# TMMOD-BREAKOUT-v1_1.net
KiCad netlist of a schematic drawn in EAGLE
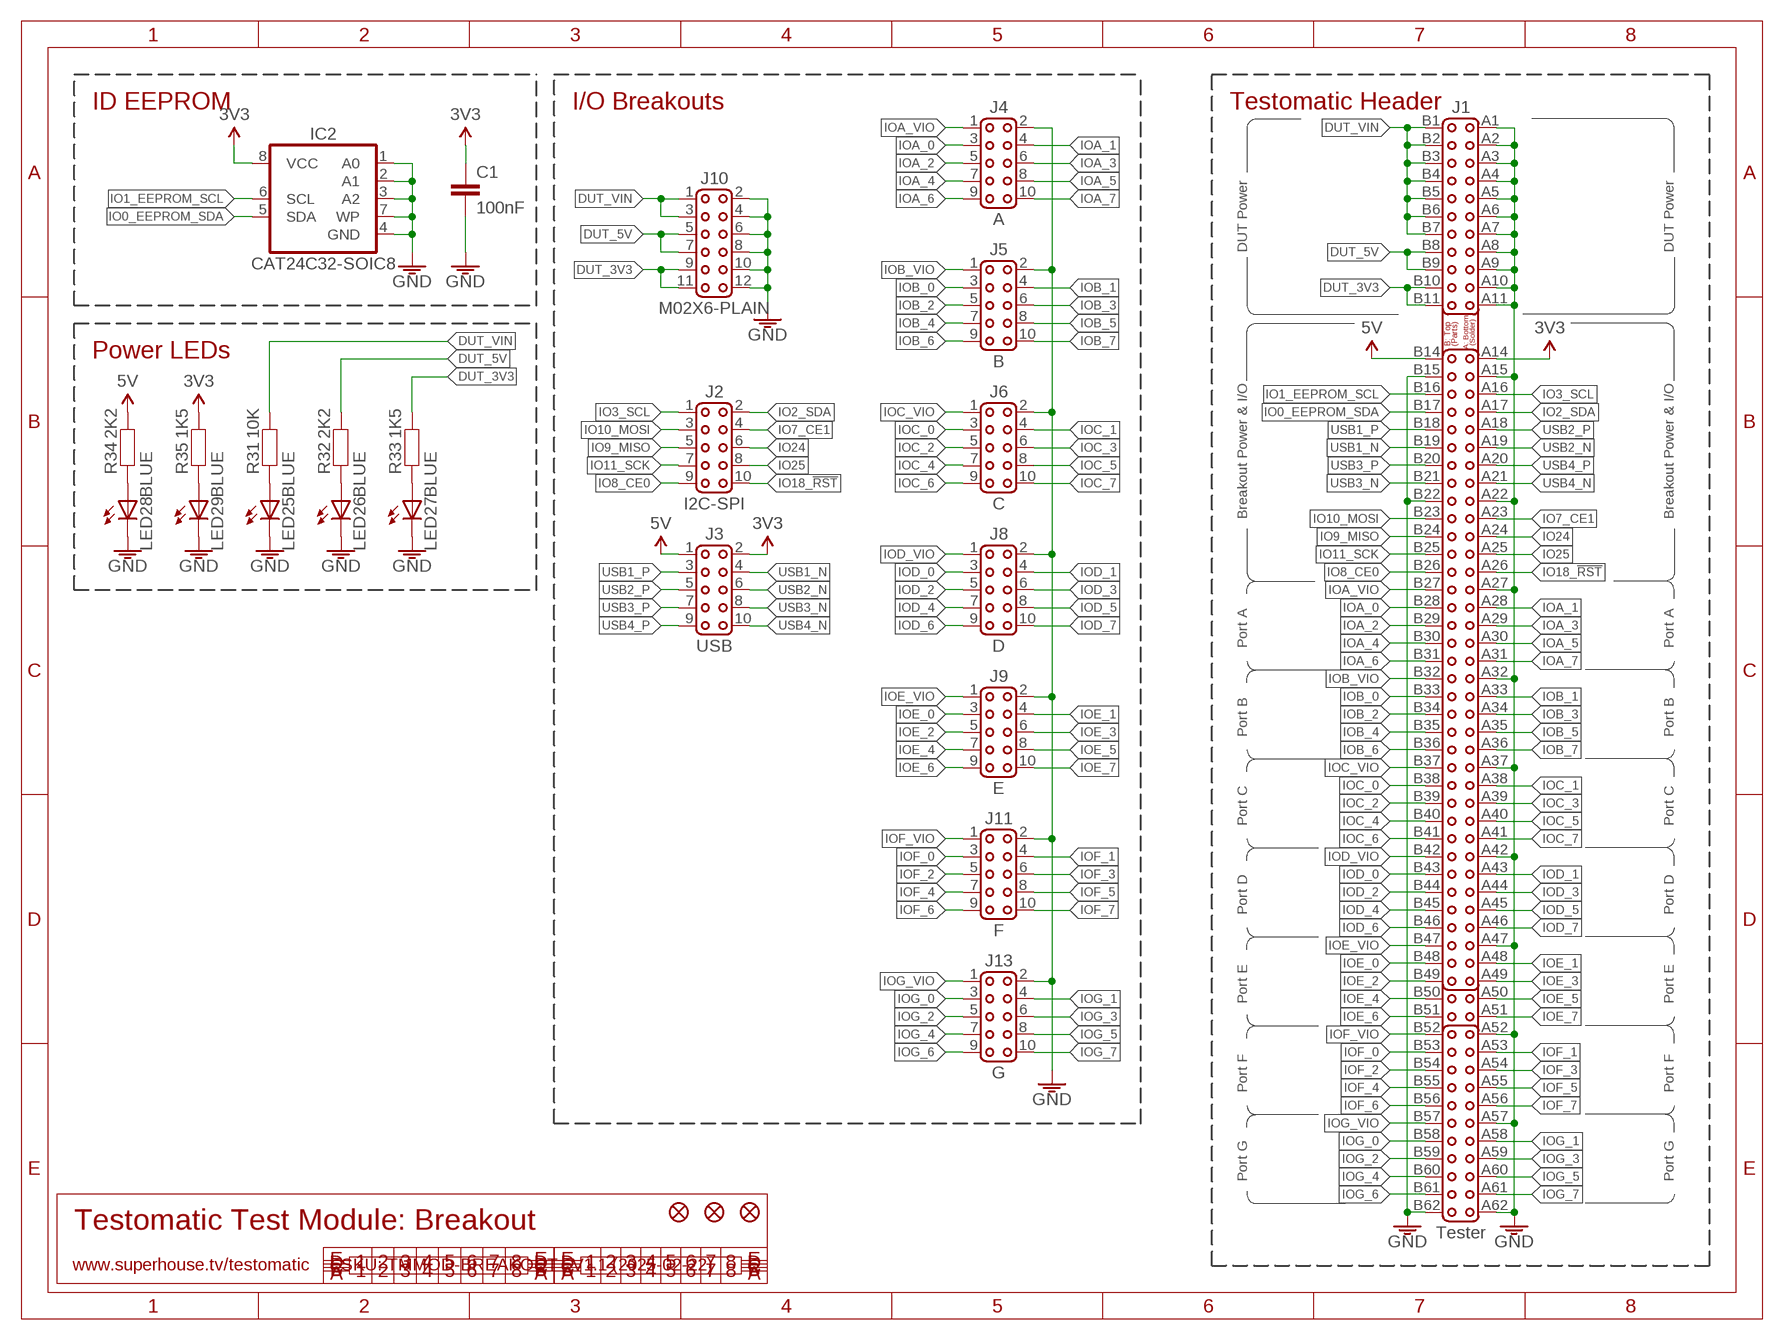
[diagram p0: schematic, sheet 1]

(export (version "E")
  (design (tool "Eeschema 10.0.6"))
  (components
    (comp (ref "C1")
      (value "100nF")
      (footprint "eagle-import:C0603")
      (libsource (lib "eagle-import") (part "CAP0603"))
    )
    (comp (ref "FID1")
      (value "FIDUCIAL1X2.5")
      (footprint "eagle-import:FIDUCIAL-1X2.5")
      (libsource (lib "eagle-import") (part "FIDUCIAL1X2.5"))
    )
    (comp (ref "FID2")
      (value "FIDUCIAL1X2.5")
      (footprint "eagle-import:FIDUCIAL-1X2.5")
      (libsource (lib "eagle-import") (part "FIDUCIAL1X2.5"))
    )
    (comp (ref "FID3")
      (value "FIDUCIAL1X2.5")
      (footprint "eagle-import:FIDUCIAL-1X2.5")
      (libsource (lib "eagle-import") (part "FIDUCIAL1X2.5"))
    )
    (comp (ref "IC2")
      (value "CAT24C32-SOIC8")
      (footprint "eagle-import:SOIC8")
      (libsource (lib "eagle-import") (part "CAT24C32-SOIC8"))
    )
    (comp (ref "J1")
      (value "Tester")
      (footprint "eagle-import:PCI-CARD")
      (libsource (lib "eagle-import") (part "PCI-CARD"))
    )
    (comp (ref "J2")
      (value "I2C-SPI")
      (footprint "eagle-import:2X05-2.54-PLAIN")
      (libsource (lib "eagle-import") (part "M02X5-PLAIN"))
    )
    (comp (ref "J3")
      (value "USB")
      (footprint "eagle-import:2X05-2.54-PLAIN")
      (libsource (lib "eagle-import") (part "M02X5-PLAIN"))
    )
    (comp (ref "J4")
      (value "A")
      (footprint "eagle-import:2X05-2.54-PLAIN")
      (libsource (lib "eagle-import") (part "M02X5-PLAIN"))
    )
    (comp (ref "J5")
      (value "B")
      (footprint "eagle-import:2X05-2.54-PLAIN")
      (libsource (lib "eagle-import") (part "M02X5-PLAIN"))
    )
    (comp (ref "J6")
      (value "C")
      (footprint "eagle-import:2X05-2.54-PLAIN")
      (libsource (lib "eagle-import") (part "M02X5-PLAIN"))
    )
    (comp (ref "J8")
      (value "D")
      (footprint "eagle-import:2X05-2.54-PLAIN")
      (libsource (lib "eagle-import") (part "M02X5-PLAIN"))
    )
    (comp (ref "J9")
      (value "E")
      (footprint "eagle-import:2X05-2.54-PLAIN")
      (libsource (lib "eagle-import") (part "M02X5-PLAIN"))
    )
    (comp (ref "J10")
      (value "M02X6-PLAIN")
      (footprint "eagle-import:2X06")
      (libsource (lib "eagle-import") (part "M02X6-PLAIN"))
    )
    (comp (ref "J11")
      (value "F")
      (footprint "eagle-import:2X05-2.54-PLAIN")
      (libsource (lib "eagle-import") (part "M02X5-PLAIN"))
    )
    (comp (ref "J13")
      (value "G")
      (footprint "eagle-import:2X05-2.54-PLAIN")
      (libsource (lib "eagle-import") (part "M02X5-PLAIN"))
    )
    (comp (ref "LED25")
      (value "BLUE")
      (footprint "eagle-import:LED-0603")
      (libsource (lib "eagle-import") (part "LED0603"))
    )
    (comp (ref "LED26")
      (value "BLUE")
      (footprint "eagle-import:LED-0603")
      (libsource (lib "eagle-import") (part "LED0603"))
    )
    (comp (ref "LED27")
      (value "BLUE")
      (footprint "eagle-import:LED-0603")
      (libsource (lib "eagle-import") (part "LED0603"))
    )
    (comp (ref "LED28")
      (value "BLUE")
      (footprint "eagle-import:LED-0603")
      (libsource (lib "eagle-import") (part "LED0603"))
    )
    (comp (ref "LED29")
      (value "BLUE")
      (footprint "eagle-import:LED-0603")
      (libsource (lib "eagle-import") (part "LED0603"))
    )
    (comp (ref "R31")
      (value "10K")
      (footprint "eagle-import:R0603")
      (libsource (lib "eagle-import") (part "RESISTOR0603"))
    )
    (comp (ref "R32")
      (value "2K2")
      (footprint "eagle-import:R0603")
      (libsource (lib "eagle-import") (part "RESISTOR0603"))
    )
    (comp (ref "R33")
      (value "1K5")
      (footprint "eagle-import:R0603")
      (libsource (lib "eagle-import") (part "RESISTOR0603"))
    )
    (comp (ref "R34")
      (value "2K2")
      (footprint "eagle-import:R0603")
      (libsource (lib "eagle-import") (part "RESISTOR0603"))
    )
    (comp (ref "R35")
      (value "1K5")
      (footprint "eagle-import:R0603")
      (libsource (lib "eagle-import") (part "RESISTOR0603"))
    )
  )
  (nets
    (net (code "1") (name "/IO18_~{RST}") (class "Default")
      (node (ref "J1") (pin "A26") (pinfunction "A26_A26") (pintype "passive"))
      (node (ref "J2") (pin "10") (pinfunction "10_10") (pintype "passive"))
    )
    (net (code "2") (name "3.3V") (class "Default")
      (node (ref "C1") (pin "1") (pinfunction "1_1") (pintype "passive"))
      (node (ref "IC2") (pin "8") (pinfunction "VCC_8") (pintype "power_in"))
      (node (ref "J1") (pin "A14") (pinfunction "A14_A14") (pintype "passive"))
      (node (ref "J3") (pin "2") (pinfunction "2_2") (pintype "passive"))
      (node (ref "R35") (pin "2") (pinfunction "2_2") (pintype "passive"))
    )
    (net (code "3") (name "5V") (class "Default")
      (node (ref "J1") (pin "B14") (pinfunction "B14_B14") (pintype "passive"))
      (node (ref "J3") (pin "1") (pinfunction "1_1") (pintype "passive"))
      (node (ref "R34") (pin "2") (pinfunction "2_2") (pintype "passive"))
    )
    (net (code "4") (name "DUT_3V3") (class "Default")
      (node (ref "J1") (pin "B10") (pinfunction "B10_B10") (pintype "passive"))
      (node (ref "J1") (pin "B11") (pinfunction "B11_B11") (pintype "passive"))
      (node (ref "J10") (pin "11") (pinfunction "11_11") (pintype "passive"))
      (node (ref "J10") (pin "9") (pinfunction "9_9") (pintype "passive"))
      (node (ref "R33") (pin "2") (pinfunction "2_2") (pintype "passive"))
    )
    (net (code "5") (name "DUT_5V") (class "Default")
      (node (ref "J1") (pin "B8") (pinfunction "B8_B8") (pintype "passive"))
      (node (ref "J1") (pin "B9") (pinfunction "B9_B9") (pintype "passive"))
      (node (ref "J10") (pin "5") (pinfunction "5_5") (pintype "passive"))
      (node (ref "J10") (pin "7") (pinfunction "7_7") (pintype "passive"))
      (node (ref "R32") (pin "2") (pinfunction "2_2") (pintype "passive"))
    )
    (net (code "6") (name "DUT_VIN") (class "Default")
      (node (ref "J1") (pin "B1") (pinfunction "B1_B1") (pintype "passive"))
      (node (ref "J1") (pin "B2") (pinfunction "B2_B2") (pintype "passive"))
      (node (ref "J1") (pin "B3") (pinfunction "B3_B3") (pintype "passive"))
      (node (ref "J1") (pin "B4") (pinfunction "B4_B4") (pintype "passive"))
      (node (ref "J1") (pin "B5") (pinfunction "B5_B5") (pintype "passive"))
      (node (ref "J1") (pin "B6") (pinfunction "B6_B6") (pintype "passive"))
      (node (ref "J1") (pin "B7") (pinfunction "B7_B7") (pintype "passive"))
      (node (ref "J10") (pin "1") (pinfunction "1_1") (pintype "passive"))
      (node (ref "J10") (pin "3") (pinfunction "3_3") (pintype "passive"))
      (node (ref "R31") (pin "2") (pinfunction "2_2") (pintype "passive"))
    )
    (net (code "7") (name "GND") (class "Default")
      (node (ref "C1") (pin "2") (pinfunction "2_2") (pintype "passive"))
      (node (ref "IC2") (pin "1") (pinfunction "A0_1") (pintype "input"))
      (node (ref "IC2") (pin "2") (pinfunction "A1_2") (pintype "input"))
      (node (ref "IC2") (pin "3") (pinfunction "A2_3") (pintype "input"))
      (node (ref "IC2") (pin "4") (pinfunction "GND_4") (pintype "power_in"))
      (node (ref "IC2") (pin "7") (pinfunction "WP_7") (pintype "bidirectional"))
      (node (ref "J1") (pin "A1") (pinfunction "A1_A1") (pintype "passive"))
      (node (ref "J1") (pin "A10") (pinfunction "A10_A10") (pintype "passive"))
      (node (ref "J1") (pin "A11") (pinfunction "A11_A11") (pintype "passive"))
      (node (ref "J1") (pin "A15") (pinfunction "A15_A15") (pintype "passive"))
      (node (ref "J1") (pin "A2") (pinfunction "A2_A2") (pintype "passive"))
      (node (ref "J1") (pin "A22") (pinfunction "A22_A22") (pintype "passive"))
      (node (ref "J1") (pin "A27") (pinfunction "A27_A27") (pintype "passive"))
      (node (ref "J1") (pin "A3") (pinfunction "A3_A3") (pintype "passive"))
      (node (ref "J1") (pin "A32") (pinfunction "A32_A32") (pintype "passive"))
      (node (ref "J1") (pin "A37") (pinfunction "A37_A37") (pintype "passive"))
      (node (ref "J1") (pin "A4") (pinfunction "A4_A4") (pintype "passive"))
      (node (ref "J1") (pin "A42") (pinfunction "A42_A42") (pintype "passive"))
      (node (ref "J1") (pin "A47") (pinfunction "A47_A47") (pintype "passive"))
      (node (ref "J1") (pin "A5") (pinfunction "A5_A5") (pintype "passive"))
      (node (ref "J1") (pin "A52") (pinfunction "A52_A52") (pintype "passive"))
      (node (ref "J1") (pin "A57") (pinfunction "A57_A57") (pintype "passive"))
      (node (ref "J1") (pin "A6") (pinfunction "A6_A6") (pintype "passive"))
      (node (ref "J1") (pin "A62") (pinfunction "A62_A62") (pintype "passive"))
      (node (ref "J1") (pin "A7") (pinfunction "A7_A7") (pintype "passive"))
      (node (ref "J1") (pin "A8") (pinfunction "A8_A8") (pintype "passive"))
      (node (ref "J1") (pin "A9") (pinfunction "A9_A9") (pintype "passive"))
      (node (ref "J1") (pin "B15") (pinfunction "B15_B15") (pintype "passive"))
      (node (ref "J1") (pin "B22") (pinfunction "B22_B22") (pintype "passive"))
      (node (ref "J1") (pin "B62") (pinfunction "B62_B62") (pintype "passive"))
      (node (ref "J10") (pin "10") (pinfunction "10_10") (pintype "passive"))
      (node (ref "J10") (pin "12") (pinfunction "12_12") (pintype "passive"))
      (node (ref "J10") (pin "2") (pinfunction "2_2") (pintype "passive"))
      (node (ref "J10") (pin "4") (pinfunction "4_4") (pintype "passive"))
      (node (ref "J10") (pin "6") (pinfunction "6_6") (pintype "passive"))
      (node (ref "J10") (pin "8") (pinfunction "8_8") (pintype "passive"))
      (node (ref "J11") (pin "2") (pinfunction "2_2") (pintype "passive"))
      (node (ref "J13") (pin "2") (pinfunction "2_2") (pintype "passive"))
      (node (ref "J4") (pin "2") (pinfunction "2_2") (pintype "passive"))
      (node (ref "J5") (pin "2") (pinfunction "2_2") (pintype "passive"))
      (node (ref "J6") (pin "2") (pinfunction "2_2") (pintype "passive"))
      (node (ref "J8") (pin "2") (pinfunction "2_2") (pintype "passive"))
      (node (ref "J9") (pin "2") (pinfunction "2_2") (pintype "passive"))
      (node (ref "LED25") (pin "C") (pinfunction "C_C") (pintype "passive"))
      (node (ref "LED26") (pin "C") (pinfunction "C_C") (pintype "passive"))
      (node (ref "LED27") (pin "C") (pinfunction "C_C") (pintype "passive"))
      (node (ref "LED28") (pin "C") (pinfunction "C_C") (pintype "passive"))
      (node (ref "LED29") (pin "C") (pinfunction "C_C") (pintype "passive"))
    )
    (net (code "8") (name "IO0_EEPROM_SDA") (class "Default")
      (node (ref "IC2") (pin "5") (pinfunction "SDA_5") (pintype "bidirectional"))
      (node (ref "J1") (pin "B17") (pinfunction "B17_B17") (pintype "passive"))
    )
    (net (code "9") (name "IO1_EEPROM_SCL") (class "Default")
      (node (ref "IC2") (pin "6") (pinfunction "SCL_6") (pintype "bidirectional"))
      (node (ref "J1") (pin "B16") (pinfunction "B16_B16") (pintype "passive"))
    )
    (net (code "10") (name "IO2_SDA") (class "Default")
      (node (ref "J1") (pin "A17") (pinfunction "A17_A17") (pintype "passive"))
      (node (ref "J2") (pin "2") (pinfunction "2_2") (pintype "passive"))
    )
    (net (code "11") (name "IO3_SCL") (class "Default")
      (node (ref "J1") (pin "A16") (pinfunction "A16_A16") (pintype "passive"))
      (node (ref "J2") (pin "1") (pinfunction "1_1") (pintype "passive"))
    )
    (net (code "12") (name "IO7_CE1") (class "Default")
      (node (ref "J1") (pin "A23") (pinfunction "A23_A23") (pintype "passive"))
      (node (ref "J2") (pin "4") (pinfunction "4_4") (pintype "passive"))
    )
    (net (code "13") (name "IO8_CE0") (class "Default")
      (node (ref "J1") (pin "B26") (pinfunction "B26_B26") (pintype "passive"))
      (node (ref "J2") (pin "9") (pinfunction "9_9") (pintype "passive"))
    )
    (net (code "14") (name "IO9_MISO") (class "Default")
      (node (ref "J1") (pin "B24") (pinfunction "B24_B24") (pintype "passive"))
      (node (ref "J2") (pin "5") (pinfunction "5_5") (pintype "passive"))
    )
    (net (code "15") (name "IO10_MOSI") (class "Default")
      (node (ref "J1") (pin "B23") (pinfunction "B23_B23") (pintype "passive"))
      (node (ref "J2") (pin "3") (pinfunction "3_3") (pintype "passive"))
    )
    (net (code "16") (name "IO11_SCK") (class "Default")
      (node (ref "J1") (pin "B25") (pinfunction "B25_B25") (pintype "passive"))
      (node (ref "J2") (pin "7") (pinfunction "7_7") (pintype "passive"))
    )
    (net (code "17") (name "IO24") (class "Default")
      (node (ref "J1") (pin "A24") (pinfunction "A24_A24") (pintype "passive"))
      (node (ref "J2") (pin "6") (pinfunction "6_6") (pintype "passive"))
    )
    (net (code "18") (name "IO25") (class "Default")
      (node (ref "J1") (pin "A25") (pinfunction "A25_A25") (pintype "passive"))
      (node (ref "J2") (pin "8") (pinfunction "8_8") (pintype "passive"))
    )
    (net (code "19") (name "IOA_0") (class "Default")
      (node (ref "J1") (pin "B28") (pinfunction "B28_B28") (pintype "passive"))
      (node (ref "J4") (pin "3") (pinfunction "3_3") (pintype "passive"))
    )
    (net (code "20") (name "IOA_1") (class "Default")
      (node (ref "J1") (pin "A28") (pinfunction "A28_A28") (pintype "passive"))
      (node (ref "J4") (pin "4") (pinfunction "4_4") (pintype "passive"))
    )
    (net (code "21") (name "IOA_2") (class "Default")
      (node (ref "J1") (pin "B29") (pinfunction "B29_B29") (pintype "passive"))
      (node (ref "J4") (pin "5") (pinfunction "5_5") (pintype "passive"))
    )
    (net (code "22") (name "IOA_3") (class "Default")
      (node (ref "J1") (pin "A29") (pinfunction "A29_A29") (pintype "passive"))
      (node (ref "J4") (pin "6") (pinfunction "6_6") (pintype "passive"))
    )
    (net (code "23") (name "IOA_4") (class "Default")
      (node (ref "J1") (pin "B30") (pinfunction "B30_B30") (pintype "passive"))
      (node (ref "J4") (pin "7") (pinfunction "7_7") (pintype "passive"))
    )
    (net (code "24") (name "IOA_5") (class "Default")
      (node (ref "J1") (pin "A30") (pinfunction "A30_A30") (pintype "passive"))
      (node (ref "J4") (pin "8") (pinfunction "8_8") (pintype "passive"))
    )
    (net (code "25") (name "IOA_6") (class "Default")
      (node (ref "J1") (pin "B31") (pinfunction "B31_B31") (pintype "passive"))
      (node (ref "J4") (pin "9") (pinfunction "9_9") (pintype "passive"))
    )
    (net (code "26") (name "IOA_7") (class "Default")
      (node (ref "J1") (pin "A31") (pinfunction "A31_A31") (pintype "passive"))
      (node (ref "J4") (pin "10") (pinfunction "10_10") (pintype "passive"))
    )
    (net (code "27") (name "IOA_VIO") (class "Default")
      (node (ref "J1") (pin "B27") (pinfunction "B27_B27") (pintype "passive"))
      (node (ref "J4") (pin "1") (pinfunction "1_1") (pintype "passive"))
    )
    (net (code "28") (name "IOB_0") (class "Default")
      (node (ref "J1") (pin "B33") (pinfunction "B33_B33") (pintype "passive"))
      (node (ref "J5") (pin "3") (pinfunction "3_3") (pintype "passive"))
    )
    (net (code "29") (name "IOB_1") (class "Default")
      (node (ref "J1") (pin "A33") (pinfunction "A33_A33") (pintype "passive"))
      (node (ref "J5") (pin "4") (pinfunction "4_4") (pintype "passive"))
    )
    (net (code "30") (name "IOB_2") (class "Default")
      (node (ref "J1") (pin "B34") (pinfunction "B34_B34") (pintype "passive"))
      (node (ref "J5") (pin "5") (pinfunction "5_5") (pintype "passive"))
    )
    (net (code "31") (name "IOB_3") (class "Default")
      (node (ref "J1") (pin "A34") (pinfunction "A34_A34") (pintype "passive"))
      (node (ref "J5") (pin "6") (pinfunction "6_6") (pintype "passive"))
    )
    (net (code "32") (name "IOB_4") (class "Default")
      (node (ref "J1") (pin "B35") (pinfunction "B35_B35") (pintype "passive"))
      (node (ref "J5") (pin "7") (pinfunction "7_7") (pintype "passive"))
    )
    (net (code "33") (name "IOB_5") (class "Default")
      (node (ref "J1") (pin "A35") (pinfunction "A35_A35") (pintype "passive"))
      (node (ref "J5") (pin "8") (pinfunction "8_8") (pintype "passive"))
    )
    (net (code "34") (name "IOB_6") (class "Default")
      (node (ref "J1") (pin "B36") (pinfunction "B36_B36") (pintype "passive"))
      (node (ref "J5") (pin "9") (pinfunction "9_9") (pintype "passive"))
    )
    (net (code "35") (name "IOB_7") (class "Default")
      (node (ref "J1") (pin "A36") (pinfunction "A36_A36") (pintype "passive"))
      (node (ref "J5") (pin "10") (pinfunction "10_10") (pintype "passive"))
    )
    (net (code "36") (name "IOB_VIO") (class "Default")
      (node (ref "J1") (pin "B32") (pinfunction "B32_B32") (pintype "passive"))
      (node (ref "J5") (pin "1") (pinfunction "1_1") (pintype "passive"))
    )
    (net (code "37") (name "IOC_0") (class "Default")
      (node (ref "J1") (pin "B38") (pinfunction "B38_B38") (pintype "passive"))
      (node (ref "J6") (pin "3") (pinfunction "3_3") (pintype "passive"))
    )
    (net (code "38") (name "IOC_1") (class "Default")
      (node (ref "J1") (pin "A38") (pinfunction "A38_A38") (pintype "passive"))
      (node (ref "J6") (pin "4") (pinfunction "4_4") (pintype "passive"))
    )
    (net (code "39") (name "IOC_2") (class "Default")
      (node (ref "J1") (pin "B39") (pinfunction "B39_B39") (pintype "passive"))
      (node (ref "J6") (pin "5") (pinfunction "5_5") (pintype "passive"))
    )
    (net (code "40") (name "IOC_3") (class "Default")
      (node (ref "J1") (pin "A39") (pinfunction "A39_A39") (pintype "passive"))
      (node (ref "J6") (pin "6") (pinfunction "6_6") (pintype "passive"))
    )
    (net (code "41") (name "IOC_4") (class "Default")
      (node (ref "J1") (pin "B40") (pinfunction "B40_B40") (pintype "passive"))
      (node (ref "J6") (pin "7") (pinfunction "7_7") (pintype "passive"))
    )
    (net (code "42") (name "IOC_5") (class "Default")
      (node (ref "J1") (pin "A40") (pinfunction "A40_A40") (pintype "passive"))
      (node (ref "J6") (pin "8") (pinfunction "8_8") (pintype "passive"))
    )
    (net (code "43") (name "IOC_6") (class "Default")
      (node (ref "J1") (pin "B41") (pinfunction "B41_B41") (pintype "passive"))
      (node (ref "J6") (pin "9") (pinfunction "9_9") (pintype "passive"))
    )
    (net (code "44") (name "IOC_7") (class "Default")
      (node (ref "J1") (pin "A41") (pinfunction "A41_A41") (pintype "passive"))
      (node (ref "J6") (pin "10") (pinfunction "10_10") (pintype "passive"))
    )
    (net (code "45") (name "IOC_VIO") (class "Default")
      (node (ref "J1") (pin "B37") (pinfunction "B37_B37") (pintype "passive"))
      (node (ref "J6") (pin "1") (pinfunction "1_1") (pintype "passive"))
    )
    (net (code "46") (name "IOD_0") (class "Default")
      (node (ref "J1") (pin "B43") (pinfunction "B43_B43") (pintype "passive"))
      (node (ref "J8") (pin "3") (pinfunction "3_3") (pintype "passive"))
    )
    (net (code "47") (name "IOD_1") (class "Default")
      (node (ref "J1") (pin "A43") (pinfunction "A43_A43") (pintype "passive"))
      (node (ref "J8") (pin "4") (pinfunction "4_4") (pintype "passive"))
    )
    (net (code "48") (name "IOD_2") (class "Default")
      (node (ref "J1") (pin "B44") (pinfunction "B44_B44") (pintype "passive"))
      (node (ref "J8") (pin "5") (pinfunction "5_5") (pintype "passive"))
    )
    (net (code "49") (name "IOD_3") (class "Default")
      (node (ref "J1") (pin "A44") (pinfunction "A44_A44") (pintype "passive"))
      (node (ref "J8") (pin "6") (pinfunction "6_6") (pintype "passive"))
    )
    (net (code "50") (name "IOD_4") (class "Default")
      (node (ref "J1") (pin "B45") (pinfunction "B45_B45") (pintype "passive"))
      (node (ref "J8") (pin "7") (pinfunction "7_7") (pintype "passive"))
    )
    (net (code "51") (name "IOD_5") (class "Default")
      (node (ref "J1") (pin "A45") (pinfunction "A45_A45") (pintype "passive"))
      (node (ref "J8") (pin "8") (pinfunction "8_8") (pintype "passive"))
    )
    (net (code "52") (name "IOD_6") (class "Default")
      (node (ref "J1") (pin "B46") (pinfunction "B46_B46") (pintype "passive"))
      (node (ref "J8") (pin "9") (pinfunction "9_9") (pintype "passive"))
    )
    (net (code "53") (name "IOD_7") (class "Default")
      (node (ref "J1") (pin "A46") (pinfunction "A46_A46") (pintype "passive"))
      (node (ref "J8") (pin "10") (pinfunction "10_10") (pintype "passive"))
    )
    (net (code "54") (name "IOD_VIO") (class "Default")
      (node (ref "J1") (pin "B42") (pinfunction "B42_B42") (pintype "passive"))
      (node (ref "J8") (pin "1") (pinfunction "1_1") (pintype "passive"))
    )
    (net (code "55") (name "IOE_0") (class "Default")
      (node (ref "J1") (pin "B48") (pinfunction "B48_B48") (pintype "passive"))
      (node (ref "J9") (pin "3") (pinfunction "3_3") (pintype "passive"))
    )
    (net (code "56") (name "IOE_1") (class "Default")
      (node (ref "J1") (pin "A48") (pinfunction "A48_A48") (pintype "passive"))
      (node (ref "J9") (pin "4") (pinfunction "4_4") (pintype "passive"))
    )
    (net (code "57") (name "IOE_2") (class "Default")
      (node (ref "J1") (pin "B49") (pinfunction "B49_B49") (pintype "passive"))
      (node (ref "J9") (pin "5") (pinfunction "5_5") (pintype "passive"))
    )
    (net (code "58") (name "IOE_3") (class "Default")
      (node (ref "J1") (pin "A49") (pinfunction "A49_A49") (pintype "passive"))
      (node (ref "J9") (pin "6") (pinfunction "6_6") (pintype "passive"))
    )
    (net (code "59") (name "IOE_4") (class "Default")
      (node (ref "J1") (pin "B50") (pinfunction "B50_B50") (pintype "passive"))
      (node (ref "J9") (pin "7") (pinfunction "7_7") (pintype "passive"))
    )
    (net (code "60") (name "IOE_5") (class "Default")
      (node (ref "J1") (pin "A50") (pinfunction "A50_A50") (pintype "passive"))
      (node (ref "J9") (pin "8") (pinfunction "8_8") (pintype "passive"))
    )
    (net (code "61") (name "IOE_6") (class "Default")
      (node (ref "J1") (pin "B51") (pinfunction "B51_B51") (pintype "passive"))
      (node (ref "J9") (pin "9") (pinfunction "9_9") (pintype "passive"))
    )
    (net (code "62") (name "IOE_7") (class "Default")
      (node (ref "J1") (pin "A51") (pinfunction "A51_A51") (pintype "passive"))
      (node (ref "J9") (pin "10") (pinfunction "10_10") (pintype "passive"))
    )
    (net (code "63") (name "IOE_VIO") (class "Default")
      (node (ref "J1") (pin "B47") (pinfunction "B47_B47") (pintype "passive"))
      (node (ref "J9") (pin "1") (pinfunction "1_1") (pintype "passive"))
    )
    (net (code "64") (name "IOF_0") (class "Default")
      (node (ref "J1") (pin "B53") (pinfunction "B53_B53") (pintype "passive"))
      (node (ref "J11") (pin "3") (pinfunction "3_3") (pintype "passive"))
    )
    (net (code "65") (name "IOF_1") (class "Default")
      (node (ref "J1") (pin "A53") (pinfunction "A53_A53") (pintype "passive"))
      (node (ref "J11") (pin "4") (pinfunction "4_4") (pintype "passive"))
    )
    (net (code "66") (name "IOF_2") (class "Default")
      (node (ref "J1") (pin "B54") (pinfunction "B54_B54") (pintype "passive"))
      (node (ref "J11") (pin "5") (pinfunction "5_5") (pintype "passive"))
    )
    (net (code "67") (name "IOF_3") (class "Default")
      (node (ref "J1") (pin "A54") (pinfunction "A54_A54") (pintype "passive"))
      (node (ref "J11") (pin "6") (pinfunction "6_6") (pintype "passive"))
    )
    (net (code "68") (name "IOF_4") (class "Default")
      (node (ref "J1") (pin "B55") (pinfunction "B55_B55") (pintype "passive"))
      (node (ref "J11") (pin "7") (pinfunction "7_7") (pintype "passive"))
    )
    (net (code "69") (name "IOF_5") (class "Default")
      (node (ref "J1") (pin "A55") (pinfunction "A55_A55") (pintype "passive"))
      (node (ref "J11") (pin "8") (pinfunction "8_8") (pintype "passive"))
    )
    (net (code "70") (name "IOF_6") (class "Default")
      (node (ref "J1") (pin "B56") (pinfunction "B56_B56") (pintype "passive"))
      (node (ref "J11") (pin "9") (pinfunction "9_9") (pintype "passive"))
    )
    (net (code "71") (name "IOF_7") (class "Default")
      (node (ref "J1") (pin "A56") (pinfunction "A56_A56") (pintype "passive"))
      (node (ref "J11") (pin "10") (pinfunction "10_10") (pintype "passive"))
    )
    (net (code "72") (name "IOF_VIO") (class "Default")
      (node (ref "J1") (pin "B52") (pinfunction "B52_B52") (pintype "passive"))
      (node (ref "J11") (pin "1") (pinfunction "1_1") (pintype "passive"))
    )
    (net (code "73") (name "IOG_0") (class "Default")
      (node (ref "J1") (pin "B58") (pinfunction "B58_B58") (pintype "passive"))
      (node (ref "J13") (pin "3") (pinfunction "3_3") (pintype "passive"))
    )
    (net (code "74") (name "IOG_1") (class "Default")
      (node (ref "J1") (pin "A58") (pinfunction "A58_A58") (pintype "passive"))
      (node (ref "J13") (pin "4") (pinfunction "4_4") (pintype "passive"))
    )
    (net (code "75") (name "IOG_2") (class "Default")
      (node (ref "J1") (pin "B59") (pinfunction "B59_B59") (pintype "passive"))
      (node (ref "J13") (pin "5") (pinfunction "5_5") (pintype "passive"))
    )
    (net (code "76") (name "IOG_3") (class "Default")
      (node (ref "J1") (pin "A59") (pinfunction "A59_A59") (pintype "passive"))
      (node (ref "J13") (pin "6") (pinfunction "6_6") (pintype "passive"))
    )
    (net (code "77") (name "IOG_4") (class "Default")
      (node (ref "J1") (pin "B60") (pinfunction "B60_B60") (pintype "passive"))
      (node (ref "J13") (pin "7") (pinfunction "7_7") (pintype "passive"))
    )
    (net (code "78") (name "IOG_5") (class "Default")
      (node (ref "J1") (pin "A60") (pinfunction "A60_A60") (pintype "passive"))
      (node (ref "J13") (pin "8") (pinfunction "8_8") (pintype "passive"))
    )
    (net (code "79") (name "IOG_6") (class "Default")
      (node (ref "J1") (pin "B61") (pinfunction "B61_B61") (pintype "passive"))
      (node (ref "J13") (pin "9") (pinfunction "9_9") (pintype "passive"))
    )
    (net (code "80") (name "IOG_7") (class "Default")
      (node (ref "J1") (pin "A61") (pinfunction "A61_A61") (pintype "passive"))
      (node (ref "J13") (pin "10") (pinfunction "10_10") (pintype "passive"))
    )
    (net (code "81") (name "IOG_VIO") (class "Default")
      (node (ref "J1") (pin "B57") (pinfunction "B57_B57") (pintype "passive"))
      (node (ref "J13") (pin "1") (pinfunction "1_1") (pintype "passive"))
    )
    (net (code "82") (name "Net-(LED25-PadA)") (class "Default")
      (node (ref "LED25") (pin "A") (pinfunction "A_A") (pintype "passive"))
      (node (ref "R31") (pin "1") (pinfunction "1_1") (pintype "passive"))
    )
    (net (code "83") (name "Net-(LED26-PadA)") (class "Default")
      (node (ref "LED26") (pin "A") (pinfunction "A_A") (pintype "passive"))
      (node (ref "R32") (pin "1") (pinfunction "1_1") (pintype "passive"))
    )
    (net (code "84") (name "Net-(LED27-PadA)") (class "Default")
      (node (ref "LED27") (pin "A") (pinfunction "A_A") (pintype "passive"))
      (node (ref "R33") (pin "1") (pinfunction "1_1") (pintype "passive"))
    )
    (net (code "85") (name "Net-(LED28-PadA)") (class "Default")
      (node (ref "LED28") (pin "A") (pinfunction "A_A") (pintype "passive"))
      (node (ref "R34") (pin "1") (pinfunction "1_1") (pintype "passive"))
    )
    (net (code "86") (name "Net-(LED29-PadA)") (class "Default")
      (node (ref "LED29") (pin "A") (pinfunction "A_A") (pintype "passive"))
      (node (ref "R35") (pin "1") (pinfunction "1_1") (pintype "passive"))
    )
    (net (code "87") (name "USB1_N") (class "Default")
      (node (ref "J1") (pin "B19") (pinfunction "B19_B19") (pintype "passive"))
      (node (ref "J3") (pin "4") (pinfunction "4_4") (pintype "passive"))
    )
    (net (code "88") (name "USB1_P") (class "Default")
      (node (ref "J1") (pin "B18") (pinfunction "B18_B18") (pintype "passive"))
      (node (ref "J3") (pin "3") (pinfunction "3_3") (pintype "passive"))
    )
    (net (code "89") (name "USB2_N") (class "Default")
      (node (ref "J1") (pin "A19") (pinfunction "A19_A19") (pintype "passive"))
      (node (ref "J3") (pin "6") (pinfunction "6_6") (pintype "passive"))
    )
    (net (code "90") (name "USB2_P") (class "Default")
      (node (ref "J1") (pin "A18") (pinfunction "A18_A18") (pintype "passive"))
      (node (ref "J3") (pin "5") (pinfunction "5_5") (pintype "passive"))
    )
    (net (code "91") (name "USB3_N") (class "Default")
      (node (ref "J1") (pin "B21") (pinfunction "B21_B21") (pintype "passive"))
      (node (ref "J3") (pin "8") (pinfunction "8_8") (pintype "passive"))
    )
    (net (code "92") (name "USB3_P") (class "Default")
      (node (ref "J1") (pin "B20") (pinfunction "B20_B20") (pintype "passive"))
      (node (ref "J3") (pin "7") (pinfunction "7_7") (pintype "passive"))
    )
    (net (code "93") (name "USB4_N") (class "Default")
      (node (ref "J1") (pin "A21") (pinfunction "A21_A21") (pintype "passive"))
      (node (ref "J3") (pin "10") (pinfunction "10_10") (pintype "passive"))
    )
    (net (code "94") (name "USB4_P") (class "Default")
      (node (ref "J1") (pin "A20") (pinfunction "A20_A20") (pintype "passive"))
      (node (ref "J3") (pin "9") (pinfunction "9_9") (pintype "passive"))
    )
  )
)
